# untitled.net
KiCad netlist of a schematic drawn in EAGLE
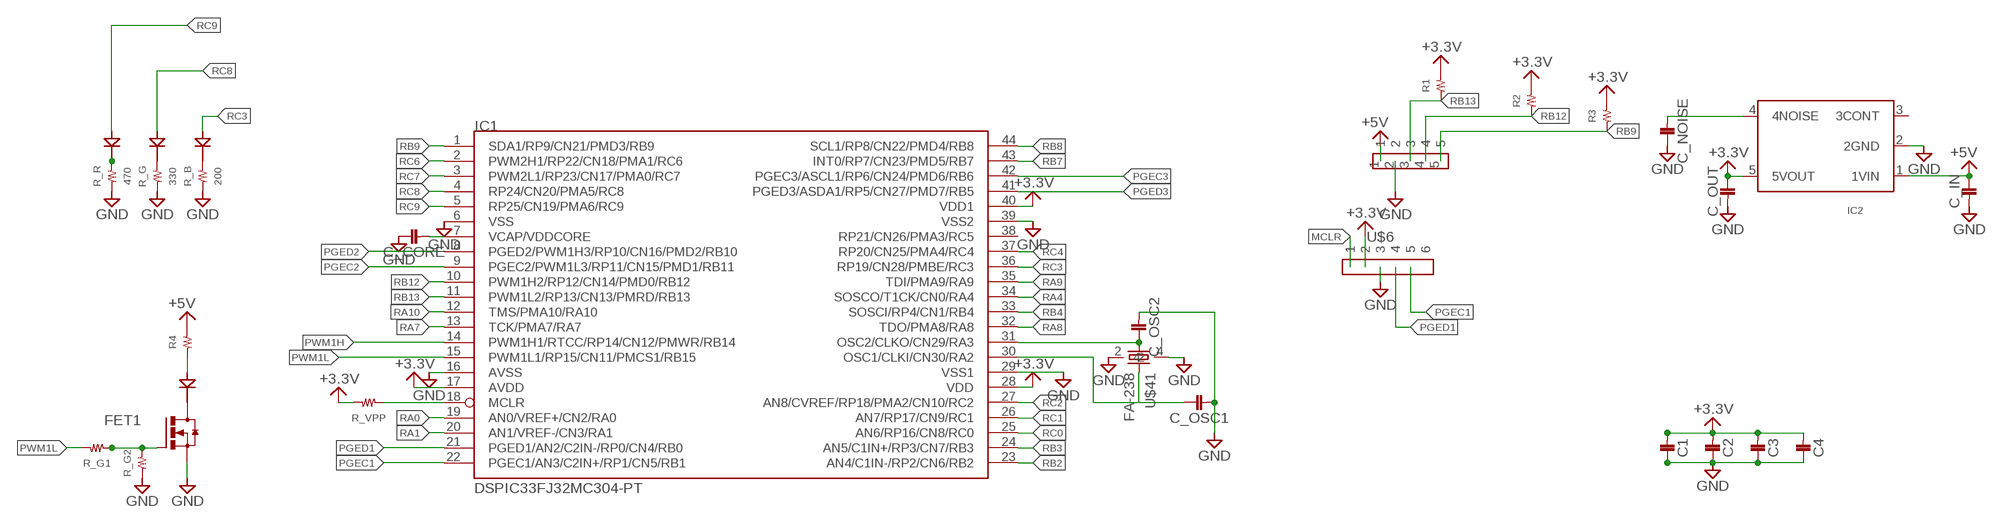
[diagram p0: schematic, sheet 1]

(export (version "E")
  (design (tool "Eeschema 10.0.6"))
  (components
    (comp (ref "B")
      (value "CHIPLED")
      (footprint "eagle-import:1608")
      (libsource (lib "eagle-import") (part "CHIPLED"))
    )
    (comp (ref "C1")
      (value "1608")
      (footprint "eagle-import:1608")
      (libsource (lib "eagle-import") (part "1608"))
    )
    (comp (ref "C2")
      (value "1608")
      (footprint "eagle-import:1608")
      (libsource (lib "eagle-import") (part "1608"))
    )
    (comp (ref "C3")
      (value "1608")
      (footprint "eagle-import:1608")
      (libsource (lib "eagle-import") (part "1608"))
    )
    (comp (ref "C4")
      (value "1608")
      (footprint "eagle-import:1608")
      (libsource (lib "eagle-import") (part "1608"))
    )
    (comp (ref "C_CORE")
      (value "2012")
      (footprint "eagle-import:2012")
      (libsource (lib "eagle-import") (part "2012"))
    )
    (comp (ref "C_IN")
      (value "1608")
      (footprint "eagle-import:1608")
      (libsource (lib "eagle-import") (part "1608"))
    )
    (comp (ref "C_NOISE")
      (value "1608")
      (footprint "eagle-import:1608")
      (libsource (lib "eagle-import") (part "1608"))
    )
    (comp (ref "C_OSC1")
      (value "1608")
      (footprint "eagle-import:1608")
      (libsource (lib "eagle-import") (part "1608"))
    )
    (comp (ref "C_OSC2")
      (value "1608")
      (footprint "eagle-import:1608")
      (libsource (lib "eagle-import") (part "1608"))
    )
    (comp (ref "C_OUT")
      (value "1608")
      (footprint "eagle-import:1608")
      (libsource (lib "eagle-import") (part "1608"))
    )
    (comp (ref "FET1")
      (value "ＩＲＬＭＬ６３４４")
      (footprint "eagle-import:SOT23")
      (libsource (lib "eagle-import") (part "ＩＲＬＭＬ６３４４"))
    )
    (comp (ref "G")
      (value "CHIPLED")
      (footprint "eagle-import:1608")
      (libsource (lib "eagle-import") (part "CHIPLED"))
    )
    (comp (ref "IC1")
      (value "DSPIC33FJ32MC304-PT")
      (footprint "eagle-import:TQFP44")
      (libsource (lib "eagle-import") (part "DSPIC33FJ32MC304-PT"))
    )
    (comp (ref "IC2")
      (value "TAR5SB")
      (footprint "eagle-import:SSOP5-P-0.95")
      (libsource (lib "eagle-import") (part "TAR5SB"))
    )
    (comp (ref "IR")
      (value "5MMLED")
      (footprint "eagle-import:5MM")
      (libsource (lib "eagle-import") (part "5MMLED"))
    )
    (comp (ref "R")
      (value "CHIPLED")
      (footprint "eagle-import:1608")
      (libsource (lib "eagle-import") (part "CHIPLED"))
    )
    (comp (ref "R1")
      (value "RESISTOR__SMD")
      (footprint "eagle-import:1608")
      (libsource (lib "eagle-import") (part "RESISTOR__SMD"))
    )
    (comp (ref "R2")
      (value "RESISTOR__SMD")
      (footprint "eagle-import:1608")
      (libsource (lib "eagle-import") (part "RESISTOR__SMD"))
    )
    (comp (ref "R3")
      (value "RESISTOR__SMD")
      (footprint "eagle-import:1608")
      (libsource (lib "eagle-import") (part "RESISTOR__SMD"))
    )
    (comp (ref "R4")
      (value "RESISTOR__SMD")
      (footprint "eagle-import:1608")
      (libsource (lib "eagle-import") (part "RESISTOR__SMD"))
    )
    (comp (ref "R_B")
      (value "200")
      (footprint "eagle-import:1608")
      (libsource (lib "eagle-import") (part "RESISTOR__SMD"))
    )
    (comp (ref "R_G")
      (value "330")
      (footprint "eagle-import:1608")
      (libsource (lib "eagle-import") (part "RESISTOR__SMD"))
    )
    (comp (ref "R_G1")
      (value "RESISTOR__SMD")
      (footprint "eagle-import:1608")
      (libsource (lib "eagle-import") (part "RESISTOR__SMD"))
    )
    (comp (ref "R_G2")
      (value "RESISTOR__SMD")
      (footprint "eagle-import:1608")
      (libsource (lib "eagle-import") (part "RESISTOR__SMD"))
    )
    (comp (ref "R_R")
      (value "470")
      (footprint "eagle-import:1608")
      (libsource (lib "eagle-import") (part "RESISTOR__SMD"))
    )
    (comp (ref "R_VPP")
      (value "RESISTOR__SMD")
      (footprint "eagle-import:1608")
      (libsource (lib "eagle-import") (part "RESISTOR__SMD"))
    )
    (comp (ref "U$6")
      (value "PIN_HEADER_6")
      (footprint "eagle-import:PIN_HEADER_6")
      (libsource (lib "eagle-import") (part "PIN_HEADER_6"))
    )
    (comp (ref "U$8")
      (value "PIN_HEADER_5")
      (footprint "eagle-import:PIN_HEADER_5")
      (libsource (lib "eagle-import") (part "PIN_HEADER_5"))
    )
    (comp (ref "U$41")
      (value "FA-238")
      (footprint "eagle-import:FA-238")
      (libsource (lib "eagle-import") (part "FA-238"))
    )
  )
  (nets
    (net (code "1") (name "+3.3V") (class "Default")
      (node (ref "C1") (pin "P$2") (pinfunction "2_P$2") (pintype "passive"))
      (node (ref "C2") (pin "P$2") (pinfunction "2_P$2") (pintype "passive"))
      (node (ref "C3") (pin "P$2") (pinfunction "2_P$2") (pintype "passive"))
      (node (ref "C4") (pin "P$2") (pinfunction "2_P$2") (pintype "passive"))
      (node (ref "C_OUT") (pin "P$1") (pinfunction "1_P$1") (pintype "passive"))
      (node (ref "IC1") (pin "17") (pinfunction "AVDD_17") (pintype "power_in"))
      (node (ref "IC1") (pin "28") (pinfunction "VDD_28") (pintype "power_in"))
      (node (ref "IC1") (pin "40") (pinfunction "VDD1_40") (pintype "power_in"))
      (node (ref "IC2") (pin "5") (pinfunction "5VOUT_5") (pintype "bidirectional"))
      (node (ref "R1") (pin "2") (pinfunction "P$2_2") (pintype "passive"))
      (node (ref "R2") (pin "2") (pinfunction "P$2_2") (pintype "passive"))
      (node (ref "R3") (pin "2") (pinfunction "P$2_2") (pintype "passive"))
      (node (ref "R_VPP") (pin "2") (pinfunction "P$2_2") (pintype "passive"))
      (node (ref "U$6") (pin "2") (pinfunction "2_2") (pintype "bidirectional"))
    )
    (net (code "2") (name "+5V") (class "Default")
      (node (ref "C_IN") (pin "P$1") (pinfunction "1_P$1") (pintype "passive"))
      (node (ref "IC2") (pin "1") (pinfunction "1VIN_1") (pintype "bidirectional"))
      (node (ref "R4") (pin "2") (pinfunction "P$2_2") (pintype "passive"))
      (node (ref "U$8") (pin "1") (pinfunction "1_1") (pintype "bidirectional"))
    )
    (net (code "3") (name "GND") (class "Default")
      (node (ref "C1") (pin "P$1") (pinfunction "1_P$1") (pintype "passive"))
      (node (ref "C2") (pin "P$1") (pinfunction "1_P$1") (pintype "passive"))
      (node (ref "C3") (pin "P$1") (pinfunction "1_P$1") (pintype "passive"))
      (node (ref "C4") (pin "P$1") (pinfunction "1_P$1") (pintype "passive"))
      (node (ref "C_CORE") (pin "1") (pinfunction "1_1") (pintype "passive"))
      (node (ref "C_IN") (pin "P$2") (pinfunction "2_P$2") (pintype "passive"))
      (node (ref "C_NOISE") (pin "P$1") (pinfunction "1_P$1") (pintype "passive"))
      (node (ref "C_OSC1") (pin "P$2") (pinfunction "2_P$2") (pintype "passive"))
      (node (ref "C_OSC2") (pin "P$2") (pinfunction "2_P$2") (pintype "passive"))
      (node (ref "C_OUT") (pin "P$2") (pinfunction "2_P$2") (pintype "passive"))
      (node (ref "FET1") (pin "2") (pinfunction "S_2") (pintype "passive"))
      (node (ref "IC1") (pin "16") (pinfunction "AVSS_16") (pintype "power_in"))
      (node (ref "IC1") (pin "29") (pinfunction "VSS1_29") (pintype "power_in"))
      (node (ref "IC1") (pin "39") (pinfunction "VSS2_39") (pintype "power_in"))
      (node (ref "IC1") (pin "6") (pinfunction "VSS_6") (pintype "power_in"))
      (node (ref "IC2") (pin "2") (pinfunction "2GND_2") (pintype "bidirectional"))
      (node (ref "R_B") (pin "1") (pinfunction "P$1_1") (pintype "passive"))
      (node (ref "R_G") (pin "1") (pinfunction "P$1_1") (pintype "passive"))
      (node (ref "R_G2") (pin "1") (pinfunction "P$1_1") (pintype "passive"))
      (node (ref "R_R") (pin "1") (pinfunction "P$1_1") (pintype "passive"))
      (node (ref "U$41") (pin "2") (pinfunction "2_2") (pintype "bidirectional"))
      (node (ref "U$41") (pin "4") (pinfunction "4_4") (pintype "bidirectional"))
      (node (ref "U$6") (pin "3") (pinfunction "3_3") (pintype "bidirectional"))
      (node (ref "U$8") (pin "2") (pinfunction "2_2") (pintype "bidirectional"))
    )
    (net (code "4") (name "MCLR") (class "Default")
      (node (ref "IC1") (pin "18") (pinfunction "MCLR_18") (pintype "input"))
      (node (ref "R_VPP") (pin "1") (pinfunction "P$1_1") (pintype "passive"))
      (node (ref "U$6") (pin "1") (pinfunction "1_1") (pintype "bidirectional"))
    )
    (net (code "5") (name "Net-(B-K)") (class "Default")
      (node (ref "B") (pin "2") (pinfunction "K_2") (pintype "bidirectional"))
      (node (ref "R_B") (pin "2") (pinfunction "P$2_2") (pintype "passive"))
    )
    (net (code "6") (name "Net-(C_NOISE-2)") (class "Default")
      (node (ref "C_NOISE") (pin "P$2") (pinfunction "2_P$2") (pintype "passive"))
      (node (ref "IC2") (pin "4") (pinfunction "4NOISE_4") (pintype "bidirectional"))
    )
    (net (code "7") (name "Net-(C_OSC1-1)") (class "Default")
      (node (ref "C_OSC1") (pin "P$1") (pinfunction "1_P$1") (pintype "passive"))
      (node (ref "IC1") (pin "30") (pinfunction "OSC1/CLKI/CN30/RA2_30") (pintype "bidirectional"))
      (node (ref "U$41") (pin "3") (pinfunction "3_3") (pintype "passive"))
    )
    (net (code "8") (name "Net-(C_OSC2-1)") (class "Default")
      (node (ref "C_OSC2") (pin "P$1") (pinfunction "1_P$1") (pintype "passive"))
      (node (ref "IC1") (pin "31") (pinfunction "OSC2/CLKO/CN29/RA3_31") (pintype "bidirectional"))
      (node (ref "U$41") (pin "1") (pinfunction "1_1") (pintype "passive"))
    )
    (net (code "9") (name "Net-(FET1-D)") (class "Default")
      (node (ref "FET1") (pin "3") (pinfunction "D_3") (pintype "passive"))
      (node (ref "IR") (pin "K") (pinfunction "K_K") (pintype "bidirectional"))
    )
    (net (code "10") (name "Net-(FET1-G)") (class "Default")
      (node (ref "FET1") (pin "1") (pinfunction "G_1") (pintype "passive"))
      (node (ref "R_G1") (pin "1") (pinfunction "P$1_1") (pintype "passive"))
      (node (ref "R_G2") (pin "2") (pinfunction "P$2_2") (pintype "passive"))
    )
    (net (code "11") (name "Net-(G-K)") (class "Default")
      (node (ref "G") (pin "2") (pinfunction "K_2") (pintype "bidirectional"))
      (node (ref "R_G") (pin "2") (pinfunction "P$2_2") (pintype "passive"))
    )
    (net (code "12") (name "Net-(IC1-VCAP{slash}VDDCORE)") (class "Default")
      (node (ref "C_CORE") (pin "2") (pinfunction "2_2") (pintype "passive"))
      (node (ref "IC1") (pin "7") (pinfunction "VCAP/VDDCORE_7") (pintype "power_in"))
    )
    (net (code "13") (name "Net-(R-K)") (class "Default")
      (node (ref "R") (pin "2") (pinfunction "K_2") (pintype "bidirectional"))
      (node (ref "R_R") (pin "2") (pinfunction "P$2_2") (pintype "passive"))
    )
    (net (code "14") (name "Net-(R4-P$1)") (class "Default")
      (node (ref "IR") (pin "A") (pinfunction "A_A") (pintype "bidirectional"))
      (node (ref "R4") (pin "1") (pinfunction "P$1_1") (pintype "passive"))
    )
    (net (code "15") (name "PGEC1") (class "Default")
      (node (ref "IC1") (pin "22") (pinfunction "PGEC1/AN3/C2IN+/RP1/CN5/RB1_22") (pintype "bidirectional"))
      (node (ref "U$6") (pin "5") (pinfunction "5_5") (pintype "bidirectional"))
    )
    (net (code "16") (name "PGEC2") (class "Default")
      (node (ref "IC1") (pin "9") (pinfunction "PGEC2/PWM1L3/RP11/CN15/PMD1/RB11_9") (pintype "bidirectional"))
    )
    (net (code "17") (name "PGEC3") (class "Default")
      (node (ref "IC1") (pin "42") (pinfunction "PGEC3/ASCL1/RP6/CN24/PMD6/RB6_42") (pintype "bidirectional"))
    )
    (net (code "18") (name "PGED1") (class "Default")
      (node (ref "IC1") (pin "21") (pinfunction "PGED1/AN2/C2IN-/RP0/CN4/RB0_21") (pintype "bidirectional"))
      (node (ref "U$6") (pin "4") (pinfunction "4_4") (pintype "bidirectional"))
    )
    (net (code "19") (name "PGED2") (class "Default")
      (node (ref "IC1") (pin "8") (pinfunction "PGED2/PWM1H3/RP10/CN16/PMD2/RB10_8") (pintype "bidirectional"))
    )
    (net (code "20") (name "PGED3") (class "Default")
      (node (ref "IC1") (pin "41") (pinfunction "PGED3/ASDA1/RP5/CN27/PMD7/RB5_41") (pintype "bidirectional"))
    )
    (net (code "21") (name "PWM1H") (class "Default")
      (node (ref "IC1") (pin "14") (pinfunction "PWM1H1/RTCC/RP14/CN12/PMWR/RB14_14") (pintype "bidirectional"))
    )
    (net (code "22") (name "PWM1L") (class "Default")
      (node (ref "IC1") (pin "15") (pinfunction "PWM1L1/RP15/CN11/PMCS1/RB15_15") (pintype "bidirectional"))
      (node (ref "R_G1") (pin "2") (pinfunction "P$2_2") (pintype "passive"))
    )
    (net (code "23") (name "RA0") (class "Default")
      (node (ref "IC1") (pin "19") (pinfunction "AN0/VREF+/CN2/RA0_19") (pintype "bidirectional"))
    )
    (net (code "24") (name "RA1") (class "Default")
      (node (ref "IC1") (pin "20") (pinfunction "AN1/VREF-/CN3/RA1_20") (pintype "bidirectional"))
    )
    (net (code "25") (name "RA4") (class "Default")
      (node (ref "IC1") (pin "34") (pinfunction "SOSCO/T1CK/CN0/RA4_34") (pintype "bidirectional"))
    )
    (net (code "26") (name "RA7") (class "Default")
      (node (ref "IC1") (pin "13") (pinfunction "TCK/PMA7/RA7_13") (pintype "bidirectional"))
    )
    (net (code "27") (name "RA8") (class "Default")
      (node (ref "IC1") (pin "32") (pinfunction "TDO/PMA8/RA8_32") (pintype "bidirectional"))
    )
    (net (code "28") (name "RA9") (class "Default")
      (node (ref "IC1") (pin "35") (pinfunction "TDI/PMA9/RA9_35") (pintype "bidirectional"))
    )
    (net (code "29") (name "RA10") (class "Default")
      (node (ref "IC1") (pin "12") (pinfunction "TMS/PMA10/RA10_12") (pintype "bidirectional"))
    )
    (net (code "30") (name "RB2") (class "Default")
      (node (ref "IC1") (pin "23") (pinfunction "AN4/C1IN-/RP2/CN6/RB2_23") (pintype "bidirectional"))
    )
    (net (code "31") (name "RB3") (class "Default")
      (node (ref "IC1") (pin "24") (pinfunction "AN5/C1IN+/RP3/CN7/RB3_24") (pintype "bidirectional"))
    )
    (net (code "32") (name "RB4") (class "Default")
      (node (ref "IC1") (pin "33") (pinfunction "SOSCI/RP4/CN1/RB4_33") (pintype "bidirectional"))
    )
    (net (code "33") (name "RB7") (class "Default")
      (node (ref "IC1") (pin "43") (pinfunction "INT0/RP7/CN23/PMD5/RB7_43") (pintype "bidirectional"))
    )
    (net (code "34") (name "RB8") (class "Default")
      (node (ref "IC1") (pin "44") (pinfunction "SCL1/RP8/CN22/PMD4/RB8_44") (pintype "bidirectional"))
    )
    (net (code "35") (name "RB9") (class "Default")
      (node (ref "IC1") (pin "1") (pinfunction "SDA1/RP9/CN21/PMD3/RB9_1") (pintype "bidirectional"))
      (node (ref "R3") (pin "1") (pinfunction "P$1_1") (pintype "passive"))
      (node (ref "U$8") (pin "5") (pinfunction "5_5") (pintype "bidirectional"))
    )
    (net (code "36") (name "RB12") (class "Default")
      (node (ref "IC1") (pin "10") (pinfunction "PWM1H2/RP12/CN14/PMD0/RB12_10") (pintype "bidirectional"))
      (node (ref "R2") (pin "1") (pinfunction "P$1_1") (pintype "passive"))
      (node (ref "U$8") (pin "4") (pinfunction "4_4") (pintype "bidirectional"))
    )
    (net (code "37") (name "RB13") (class "Default")
      (node (ref "IC1") (pin "11") (pinfunction "PWM1L2/RP13/CN13/PMRD/RB13_11") (pintype "bidirectional"))
      (node (ref "R1") (pin "1") (pinfunction "P$1_1") (pintype "passive"))
      (node (ref "U$8") (pin "3") (pinfunction "3_3") (pintype "bidirectional"))
    )
    (net (code "38") (name "RC0") (class "Default")
      (node (ref "IC1") (pin "25") (pinfunction "AN6/RP16/CN8/RC0_25") (pintype "bidirectional"))
    )
    (net (code "39") (name "RC1") (class "Default")
      (node (ref "IC1") (pin "26") (pinfunction "AN7/RP17/CN9/RC1_26") (pintype "bidirectional"))
    )
    (net (code "40") (name "RC2") (class "Default")
      (node (ref "IC1") (pin "27") (pinfunction "AN8/CVREF/RP18/PMA2/CN10/RC2_27") (pintype "bidirectional"))
    )
    (net (code "41") (name "RC3") (class "Default")
      (node (ref "B") (pin "1") (pinfunction "A_1") (pintype "bidirectional"))
      (node (ref "IC1") (pin "36") (pinfunction "RP19/CN28/PMBE/RC3_36") (pintype "bidirectional"))
    )
    (net (code "42") (name "RC4") (class "Default")
      (node (ref "IC1") (pin "37") (pinfunction "RP20/CN25/PMA4/RC4_37") (pintype "bidirectional"))
    )
    (net (code "43") (name "RC6") (class "Default")
      (node (ref "IC1") (pin "2") (pinfunction "PWM2H1/RP22/CN18/PMA1/RC6_2") (pintype "bidirectional"))
    )
    (net (code "44") (name "RC7") (class "Default")
      (node (ref "IC1") (pin "3") (pinfunction "PWM2L1/RP23/CN17/PMA0/RC7_3") (pintype "bidirectional"))
    )
    (net (code "45") (name "RC8") (class "Default")
      (node (ref "G") (pin "1") (pinfunction "A_1") (pintype "bidirectional"))
      (node (ref "IC1") (pin "4") (pinfunction "RP24/CN20/PMA5/RC8_4") (pintype "bidirectional"))
    )
    (net (code "46") (name "RC9") (class "Default")
      (node (ref "IC1") (pin "5") (pinfunction "RP25/CN19/PMA6/RC9_5") (pintype "bidirectional"))
      (node (ref "R") (pin "1") (pinfunction "A_1") (pintype "bidirectional"))
    )
    (net (code "47") (name "unconnected-(IC1-RP21{slash}CN26{slash}PMA3{slash}RC5-Pad38)") (class "Default")
      (node (ref "IC1") (pin "38") (pinfunction "RP21/CN26/PMA3/RC5_38") (pintype "bidirectional"))
    )
    (net (code "48") (name "unconnected-(IC2-3CONT-Pad3)") (class "Default")
      (node (ref "IC2") (pin "3") (pinfunction "3CONT_3") (pintype "bidirectional"))
    )
    (net (code "49") (name "unconnected-(U$6-Pad6)") (class "Default")
      (node (ref "U$6") (pin "6") (pinfunction "6_6") (pintype "bidirectional"))
    )
  )
)
